# twometertx-micrf300.net
KiCad netlist of a schematic drawn in EAGLE
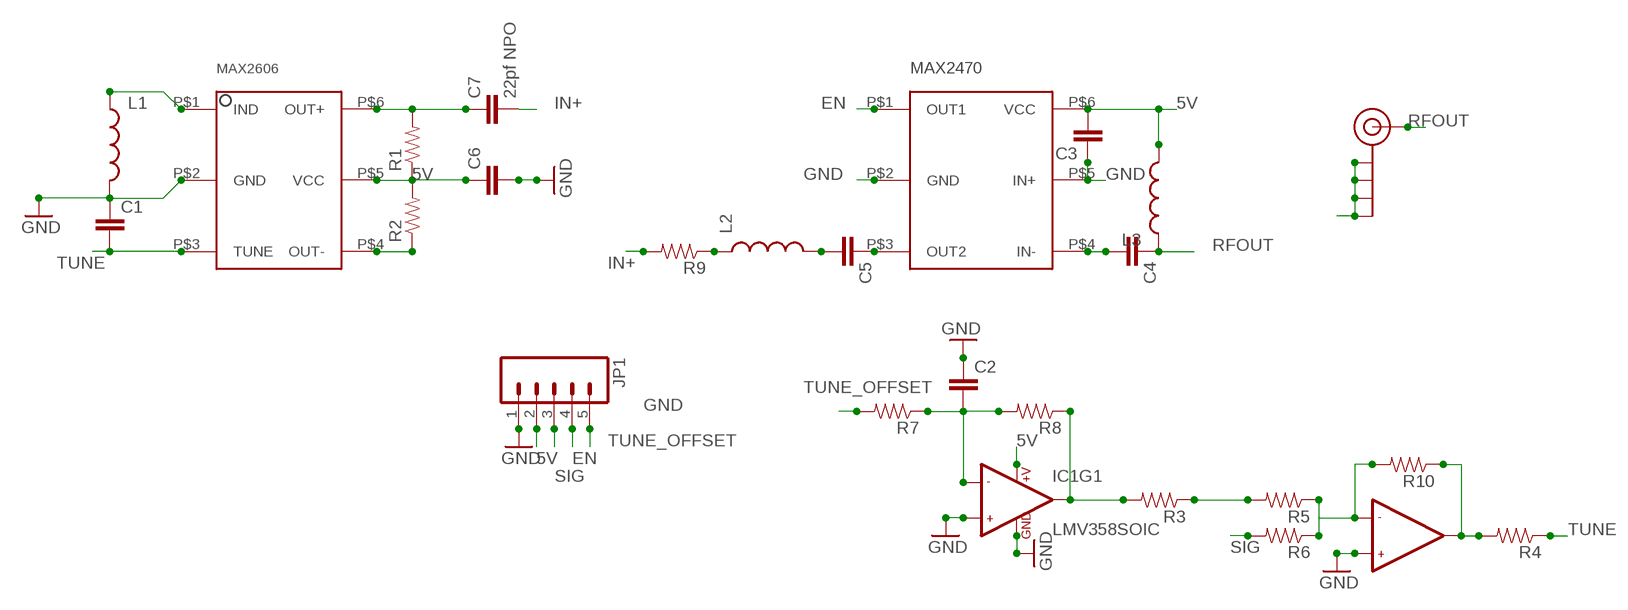
[diagram p0: schematic, sheet 1]

(export (version "E")
  (design (tool "Eeschema 10.0.6"))
  (components
    (comp (ref "C1")
      (value "CAP0805")
      (footprint "eagle-import:0805")
      (libsource (lib "eagle-import") (part "CAP0805"))
    )
    (comp (ref "C2")
      (value "CAP0805")
      (footprint "eagle-import:0805")
      (libsource (lib "eagle-import") (part "CAP0805"))
    )
    (comp (ref "C3")
      (value "CAP0805")
      (footprint "eagle-import:0805")
      (libsource (lib "eagle-import") (part "CAP0805"))
    )
    (comp (ref "C4")
      (value "CAP0805")
      (footprint "eagle-import:0805")
      (libsource (lib "eagle-import") (part "CAP0805"))
    )
    (comp (ref "C5")
      (value "CAP0805")
      (footprint "eagle-import:0805")
      (libsource (lib "eagle-import") (part "CAP0805"))
    )
    (comp (ref "C6")
      (value "CAP0805")
      (footprint "eagle-import:0805")
      (libsource (lib "eagle-import") (part "CAP0805"))
    )
    (comp (ref "C7")
      (value "22pf NPO")
      (footprint "eagle-import:0805")
      (libsource (lib "eagle-import") (part "CAP0805"))
    )
    (comp (ref "IC1")
      (value "LMV358SOIC")
      (footprint "eagle-import:SO08")
      (libsource (lib "eagle-import") (part "LMV358SOIC"))
    )
    (comp (ref "J$1")
      (value "SMA_EDGE")
      (footprint "eagle-import:SMA-EDGE")
      (libsource (lib "eagle-import") (part "SMA_EDGE"))
    )
    (comp (ref "JP1")
      (value "M05PTH_LONGPADS")
      (footprint "eagle-import:1X05_LONGPADS")
      (libsource (lib "eagle-import") (part "M05PTH_LONGPADS"))
    )
    (comp (ref "L1")
      (value "INDUCTOR0805")
      (footprint "eagle-import:0805")
      (libsource (lib "eagle-import") (part "INDUCTOR0805"))
    )
    (comp (ref "L2")
      (value "INDUCTOR0805")
      (footprint "eagle-import:0805")
      (libsource (lib "eagle-import") (part "INDUCTOR0805"))
    )
    (comp (ref "L3")
      (value "INDUCTOR0805")
      (footprint "eagle-import:0805")
      (libsource (lib "eagle-import") (part "INDUCTOR0805"))
    )
    (comp (ref "R1")
      (value "RESISTOR0805-RES")
      (footprint "eagle-import:0805")
      (libsource (lib "eagle-import") (part "RESISTOR0805-RES"))
    )
    (comp (ref "R2")
      (value "RESISTOR0805-RES")
      (footprint "eagle-import:0805")
      (libsource (lib "eagle-import") (part "RESISTOR0805-RES"))
    )
    (comp (ref "R3")
      (value "RESISTOR0805-RES")
      (footprint "eagle-import:0805")
      (libsource (lib "eagle-import") (part "RESISTOR0805-RES"))
    )
    (comp (ref "R4")
      (value "RESISTOR0805-RES")
      (footprint "eagle-import:0805")
      (libsource (lib "eagle-import") (part "RESISTOR0805-RES"))
    )
    (comp (ref "R5")
      (value "RESISTOR0805-RES")
      (footprint "eagle-import:0805")
      (libsource (lib "eagle-import") (part "RESISTOR0805-RES"))
    )
    (comp (ref "R6")
      (value "RESISTOR0805-RES")
      (footprint "eagle-import:0805")
      (libsource (lib "eagle-import") (part "RESISTOR0805-RES"))
    )
    (comp (ref "R7")
      (value "RESISTOR0805-RES")
      (footprint "eagle-import:0805")
      (libsource (lib "eagle-import") (part "RESISTOR0805-RES"))
    )
    (comp (ref "R8")
      (value "RESISTOR0805-RES")
      (footprint "eagle-import:0805")
      (libsource (lib "eagle-import") (part "RESISTOR0805-RES"))
    )
    (comp (ref "R9")
      (value "RESISTOR0805-RES")
      (footprint "eagle-import:0805")
      (libsource (lib "eagle-import") (part "RESISTOR0805-RES"))
    )
    (comp (ref "R10")
      (value "RESISTOR0805-RES")
      (footprint "eagle-import:0805")
      (libsource (lib "eagle-import") (part "RESISTOR0805-RES"))
    )
    (comp (ref "U$1")
      (value "MAX2606")
      (footprint "eagle-import:MAX2606")
      (libsource (lib "eagle-import") (part "MAX2606"))
    )
    (comp (ref "U$2")
      (value "MAX2470")
      (footprint "eagle-import:MAX2470")
      (libsource (lib "eagle-import") (part "MAX2470"))
    )
  )
  (nets
    (net (code "1") (name "/5V") (class "Default")
      (node (ref "C3") (pin "2") (pinfunction "2_2") (pintype "passive"))
      (node (ref "C6") (pin "1") (pinfunction "1_1") (pintype "passive"))
      (node (ref "IC1") (pin "8") (pinfunction "+V_8") (pintype "power_in"))
      (node (ref "JP1") (pin "2") (pinfunction "2_2") (pintype "passive"))
      (node (ref "L3") (pin "2") (pinfunction "2_2") (pintype "passive"))
      (node (ref "R1") (pin "1") (pinfunction "1_1") (pintype "passive"))
      (node (ref "R2") (pin "2") (pinfunction "2_2") (pintype "passive"))
      (node (ref "U$1") (pin "P$5") (pinfunction "VCC_P$5") (pintype "bidirectional"))
      (node (ref "U$2") (pin "P$6") (pinfunction "VCC_P$6") (pintype "bidirectional"))
    )
    (net (code "2") (name "/EN") (class "Default")
      (node (ref "JP1") (pin "4") (pinfunction "4_4") (pintype "passive"))
      (node (ref "U$2") (pin "P$1") (pinfunction "OUT1_P$1") (pintype "bidirectional"))
    )
    (net (code "3") (name "/IN+") (class "Default")
      (node (ref "C7") (pin "2") (pinfunction "2_2") (pintype "passive"))
      (node (ref "R9") (pin "2") (pinfunction "2_2") (pintype "passive"))
    )
    (net (code "4") (name "/RFOUT") (class "Default")
      (node (ref "C4") (pin "1") (pinfunction "1_1") (pintype "passive"))
      (node (ref "J$1") (pin "SIG") (pinfunction "SIGNAL_SIG") (pintype "bidirectional"))
      (node (ref "L3") (pin "1") (pinfunction "1_1") (pintype "passive"))
    )
    (net (code "5") (name "/SIG") (class "Default")
      (node (ref "JP1") (pin "3") (pinfunction "3_3") (pintype "passive"))
      (node (ref "R6") (pin "2") (pinfunction "2_2") (pintype "passive"))
    )
    (net (code "6") (name "/TUNE") (class "Default")
      (node (ref "C1") (pin "2") (pinfunction "2_2") (pintype "passive"))
      (node (ref "R4") (pin "1") (pinfunction "1_1") (pintype "passive"))
      (node (ref "U$1") (pin "P$3") (pinfunction "TUNE_P$3") (pintype "bidirectional"))
    )
    (net (code "7") (name "/TUNE_OFFSET") (class "Default")
      (node (ref "JP1") (pin "5") (pinfunction "5_5") (pintype "passive"))
      (node (ref "R7") (pin "2") (pinfunction "2_2") (pintype "passive"))
    )
    (net (code "8") (name "GND") (class "Default")
      (node (ref "C1") (pin "1") (pinfunction "1_1") (pintype "passive"))
      (node (ref "C2") (pin "1") (pinfunction "1_1") (pintype "passive"))
      (node (ref "C3") (pin "1") (pinfunction "1_1") (pintype "passive"))
      (node (ref "C4") (pin "2") (pinfunction "2_2") (pintype "passive"))
      (node (ref "C6") (pin "2") (pinfunction "2_2") (pintype "passive"))
      (node (ref "IC1") (pin "3") (pinfunction "+IN1_3") (pintype "input"))
      (node (ref "IC1") (pin "4") (pinfunction "GND_4") (pintype "power_in"))
      (node (ref "IC1") (pin "5") (pinfunction "+IN2_5") (pintype "input"))
      (node (ref "J$1") (pin "GND@0") (pinfunction "GND_GND@0") (pintype "bidirectional"))
      (node (ref "J$1") (pin "GND@1") (pinfunction "GND_GND@1") (pintype "bidirectional"))
      (node (ref "J$1") (pin "GND@2") (pinfunction "GND_GND@2") (pintype "bidirectional"))
      (node (ref "J$1") (pin "GND@3") (pinfunction "GND_GND@3") (pintype "bidirectional"))
      (node (ref "JP1") (pin "1") (pinfunction "1_1") (pintype "passive"))
      (node (ref "L1") (pin "2") (pinfunction "2_2") (pintype "passive"))
      (node (ref "U$1") (pin "P$2") (pinfunction "GND_P$2") (pintype "bidirectional"))
      (node (ref "U$2") (pin "P$2") (pinfunction "GND_P$2") (pintype "bidirectional"))
      (node (ref "U$2") (pin "P$4") (pinfunction "IN-_P$4") (pintype "bidirectional"))
      (node (ref "U$2") (pin "P$5") (pinfunction "IN+_P$5") (pintype "bidirectional"))
    )
    (net (code "9") (name "Net-(C5-Pad2)") (class "Default")
      (node (ref "C5") (pin "2") (pinfunction "2_2") (pintype "passive"))
      (node (ref "L2") (pin "2") (pinfunction "2_2") (pintype "passive"))
    )
    (net (code "10") (name "Net-(IC1A--IN1)") (class "Default")
      (node (ref "C2") (pin "2") (pinfunction "2_2") (pintype "passive"))
      (node (ref "IC1") (pin "2") (pinfunction "-IN1_2") (pintype "input"))
      (node (ref "R7") (pin "1") (pinfunction "1_1") (pintype "passive"))
      (node (ref "R8") (pin "2") (pinfunction "2_2") (pintype "passive"))
    )
    (net (code "11") (name "Net-(IC1A-OUT1)") (class "Default")
      (node (ref "IC1") (pin "1") (pinfunction "OUT1_1") (pintype "output"))
      (node (ref "R3") (pin "2") (pinfunction "2_2") (pintype "passive"))
      (node (ref "R8") (pin "1") (pinfunction "1_1") (pintype "passive"))
    )
    (net (code "12") (name "Net-(IC1B--IN2)") (class "Default")
      (node (ref "IC1") (pin "6") (pinfunction "-IN2_6") (pintype "input"))
      (node (ref "R10") (pin "2") (pinfunction "2_2") (pintype "passive"))
      (node (ref "R5") (pin "1") (pinfunction "1_1") (pintype "passive"))
      (node (ref "R6") (pin "1") (pinfunction "1_1") (pintype "passive"))
    )
    (net (code "13") (name "Net-(IC1B-OUT2)") (class "Default")
      (node (ref "IC1") (pin "7") (pinfunction "OUT2_7") (pintype "output"))
      (node (ref "R10") (pin "1") (pinfunction "1_1") (pintype "passive"))
      (node (ref "R4") (pin "2") (pinfunction "2_2") (pintype "passive"))
    )
    (net (code "14") (name "Net-(L2-Pad1)") (class "Default")
      (node (ref "L2") (pin "1") (pinfunction "1_1") (pintype "passive"))
      (node (ref "R9") (pin "1") (pinfunction "1_1") (pintype "passive"))
    )
    (net (code "15") (name "Net-(R3-Pad1)") (class "Default")
      (node (ref "R3") (pin "1") (pinfunction "1_1") (pintype "passive"))
      (node (ref "R5") (pin "2") (pinfunction "2_2") (pintype "passive"))
    )
    (net (code "16") (name "Net-(U$1-IND)") (class "Default")
      (node (ref "L1") (pin "1") (pinfunction "1_1") (pintype "passive"))
      (node (ref "U$1") (pin "P$1") (pinfunction "IND_P$1") (pintype "bidirectional"))
    )
    (net (code "17") (name "Net-(U$1-OUT+)") (class "Default")
      (node (ref "C7") (pin "1") (pinfunction "1_1") (pintype "passive"))
      (node (ref "R1") (pin "2") (pinfunction "2_2") (pintype "passive"))
      (node (ref "U$1") (pin "P$6") (pinfunction "OUT+_P$6") (pintype "bidirectional"))
    )
    (net (code "18") (name "Net-(U$1-OUT-)") (class "Default")
      (node (ref "R2") (pin "1") (pinfunction "1_1") (pintype "passive"))
      (node (ref "U$1") (pin "P$4") (pinfunction "OUT-_P$4") (pintype "bidirectional"))
    )
    (net (code "19") (name "Net-(U$2-OUT2)") (class "Default")
      (node (ref "C5") (pin "1") (pinfunction "1_1") (pintype "passive"))
      (node (ref "U$2") (pin "P$3") (pinfunction "OUT2_P$3") (pintype "bidirectional"))
    )
  )
)
